# Esquema.net
KiCad netlist of a schematic drawn in EAGLE
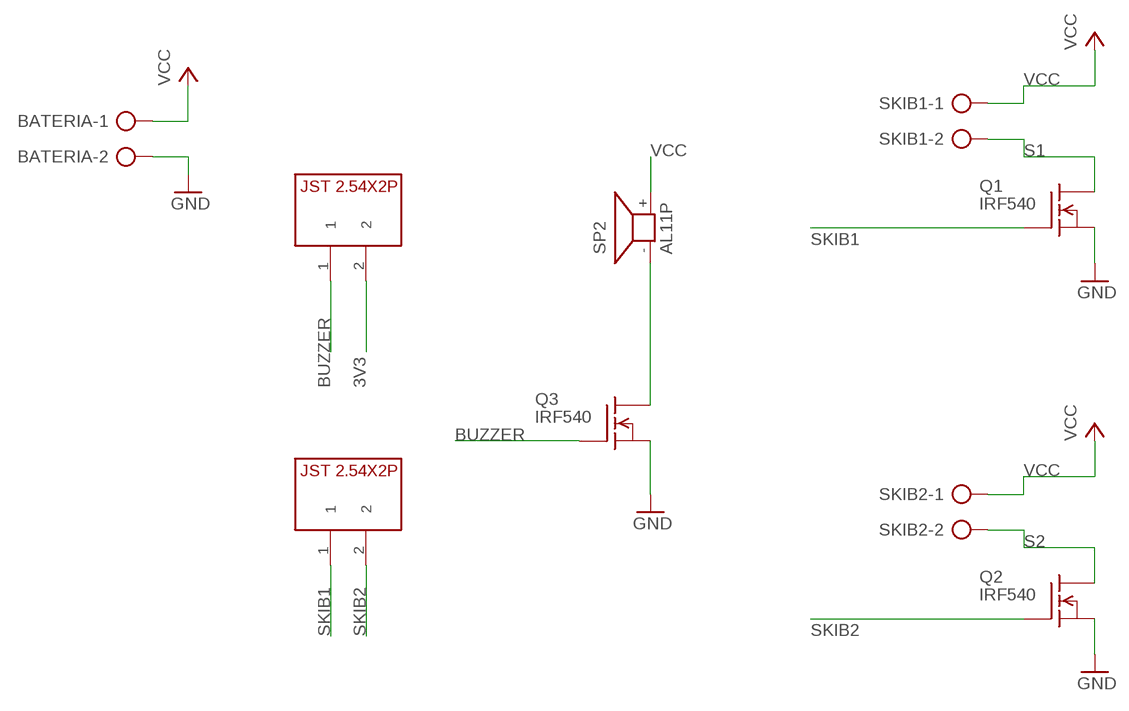
[diagram p0: schematic, sheet 1]

(export (version "E")
  (design (tool "Eeschema 10.0.6"))
  (components
    (comp (ref "BATERIA")
      (value "AK500/2-H")
      (footprint "eagle-import:AK500_2-H")
      (libsource (lib "eagle-import") (part "AK500/2-H"))
    )
    (comp (ref "Q1")
      (value "IRF540")
      (footprint "eagle-import:TO220")
      (libsource (lib "eagle-import") (part "IRF540"))
    )
    (comp (ref "Q2")
      (value "IRF540")
      (footprint "eagle-import:TO220")
      (libsource (lib "eagle-import") (part "IRF540"))
    )
    (comp (ref "Q3")
      (value "IRF540")
      (footprint "eagle-import:TO220")
      (libsource (lib "eagle-import") (part "IRF540"))
    )
    (comp (ref "SKIB1")
      (value "AK500/2-H")
      (footprint "eagle-import:AK500_2-H")
      (libsource (lib "eagle-import") (part "AK500/2-H"))
    )
    (comp (ref "SKIB2")
      (value "AK500/2-H")
      (footprint "eagle-import:AK500_2-H")
      (libsource (lib "eagle-import") (part "AK500/2-H"))
    )
    (comp (ref "SP2")
      (value "AL11P")
      (footprint "eagle-import:AL11P")
      (libsource (lib "eagle-import") (part "AL11P"))
    )
    (comp (ref "U$1")
      (value "JST2.54X2P")
      (footprint "eagle-import:JST2.54X2P_FOOTPRINT")
      (libsource (lib "eagle-import") (part "JST2.54X2P"))
    )
    (comp (ref "U$2")
      (value "JST2.54X2P")
      (footprint "eagle-import:JST2.54X2P_FOOTPRINT")
      (libsource (lib "eagle-import") (part "JST2.54X2P"))
    )
  )
  (nets
    (net (code "1") (name "/3V3") (class "Default")
      (node (ref "U$1") (pin "2") (pinfunction "2_2") (pintype "bidirectional"))
    )
    (net (code "2") (name "/BUZZER") (class "Default")
      (node (ref "Q3") (pin "1") (pinfunction "G_1") (pintype "passive"))
      (node (ref "U$1") (pin "1") (pinfunction "1_1") (pintype "bidirectional"))
    )
    (net (code "3") (name "/S1") (class "Default")
      (node (ref "Q1") (pin "2") (pinfunction "D_2") (pintype "passive"))
      (node (ref "SKIB1") (pin "2") (pinfunction "KL_2") (pintype "passive"))
    )
    (net (code "4") (name "/S2") (class "Default")
      (node (ref "Q2") (pin "2") (pinfunction "D_2") (pintype "passive"))
      (node (ref "SKIB2") (pin "2") (pinfunction "KL_2") (pintype "passive"))
    )
    (net (code "5") (name "/SKIB1") (class "Default")
      (node (ref "Q1") (pin "1") (pinfunction "G_1") (pintype "passive"))
      (node (ref "U$2") (pin "1") (pinfunction "1_1") (pintype "bidirectional"))
    )
    (net (code "6") (name "/SKIB2") (class "Default")
      (node (ref "Q2") (pin "1") (pinfunction "G_1") (pintype "passive"))
      (node (ref "U$2") (pin "2") (pinfunction "2_2") (pintype "bidirectional"))
    )
    (net (code "7") (name "GND") (class "Default")
      (node (ref "BATERIA") (pin "2") (pinfunction "KL_2") (pintype "passive"))
      (node (ref "Q1") (pin "3") (pinfunction "S_3") (pintype "passive"))
      (node (ref "Q2") (pin "3") (pinfunction "S_3") (pintype "passive"))
      (node (ref "Q3") (pin "3") (pinfunction "S_3") (pintype "passive"))
    )
    (net (code "8") (name "Net-(Q3-D)") (class "Default")
      (node (ref "Q3") (pin "2") (pinfunction "D_2") (pintype "passive"))
      (node (ref "SP2") (pin "-") (pinfunction "1_-") (pintype "passive"))
    )
    (net (code "9") (name "VCC") (class "Default")
      (node (ref "BATERIA") (pin "1") (pinfunction "KL_1") (pintype "passive"))
      (node (ref "SKIB1") (pin "1") (pinfunction "KL_1") (pintype "passive"))
      (node (ref "SKIB2") (pin "1") (pinfunction "KL_1") (pintype "passive"))
      (node (ref "SP2") (pin "+") (pinfunction "2_+") (pintype "passive"))
    )
  )
)
